# USB_Audio.net
KiCad netlist of a schematic drawn in Altium Designer
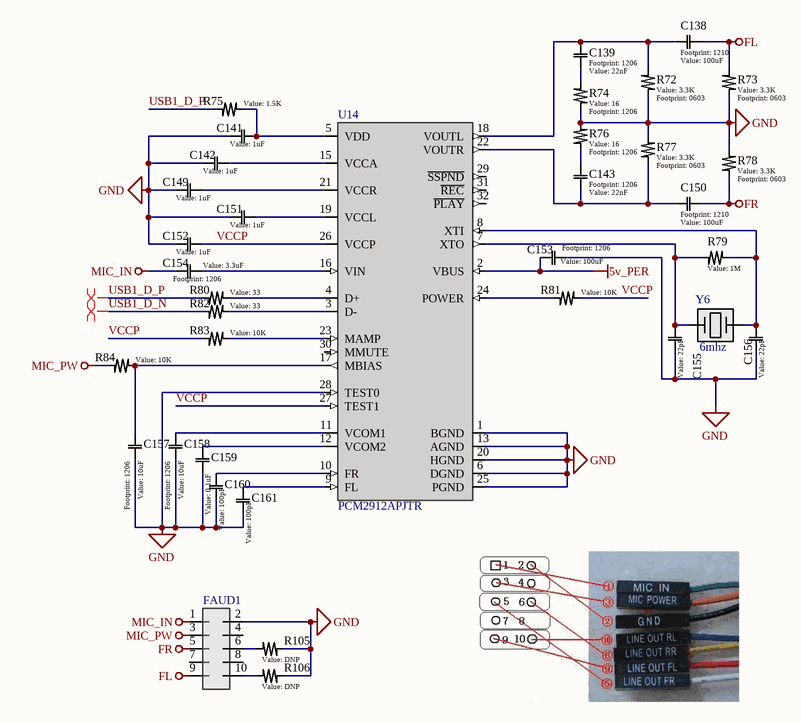
[diagram p0: USB_Audio.SchDoc]

(export (version "E")
  (design (tool "Eeschema 10.0.6"))
  (components
    (comp (ref "C138")
      (value "100uF")
      (footprint "1210")
      (fields
        (field (name "VOLTAGE") ">10V")
        (field (name "TOLERANCE") "10%")
        (field (name "Comment") "Generic Capacitor")
      )
      (libsource (lib "Capacitors") (part "Generic Capacitor"))
    )
    (comp (ref "C139")
      (value "22nF")
      (footprint "1206")
      (fields
        (field (name "VOLTAGE") ">10V")
        (field (name "TOLERANCE") "10%")
        (field (name "Comment") "Generic Capacitor")
      )
      (libsource (lib "Capacitors") (part "Generic Capacitor"))
    )
    (comp (ref "C141")
      (value "1uF")
      (footprint "0603")
      (fields
        (field (name "VOLTAGE") ">10V")
        (field (name "TOLERANCE") "10%")
        (field (name "Comment") "Generic Capacitor")
      )
      (libsource (lib "Capacitors") (part "Generic Capacitor"))
    )
    (comp (ref "C142")
      (value "1uF")
      (footprint "0603")
      (fields
        (field (name "VOLTAGE") ">10V")
        (field (name "TOLERANCE") "10%")
        (field (name "Comment") "Generic Capacitor")
      )
      (libsource (lib "Capacitors") (part "Generic Capacitor"))
    )
    (comp (ref "C143")
      (value "22nF")
      (footprint "1206")
      (fields
        (field (name "VOLTAGE") ">10V")
        (field (name "TOLERANCE") "10%")
        (field (name "Comment") "Generic Capacitor")
      )
      (libsource (lib "Capacitors") (part "Generic Capacitor"))
    )
    (comp (ref "C149")
      (value "1uF")
      (footprint "0603")
      (fields
        (field (name "VOLTAGE") ">10V")
        (field (name "TOLERANCE") "10%")
        (field (name "Comment") "Generic Capacitor")
      )
      (libsource (lib "Capacitors") (part "Generic Capacitor"))
    )
    (comp (ref "C150")
      (value "100uF")
      (footprint "1210")
      (fields
        (field (name "VOLTAGE") ">10V")
        (field (name "TOLERANCE") "10%")
        (field (name "Comment") "Generic Capacitor")
      )
      (libsource (lib "Capacitors") (part "Generic Capacitor"))
    )
    (comp (ref "C151")
      (value "1uF")
      (footprint "0603")
      (fields
        (field (name "VOLTAGE") ">10V")
        (field (name "TOLERANCE") "10%")
        (field (name "Comment") "Generic Capacitor")
      )
      (libsource (lib "Capacitors") (part "Generic Capacitor"))
    )
    (comp (ref "C152")
      (value "1uF")
      (footprint "0603")
      (fields
        (field (name "VOLTAGE") ">10V")
        (field (name "TOLERANCE") "10%")
        (field (name "Comment") "Generic Capacitor")
      )
      (libsource (lib "Capacitors") (part "Generic Capacitor"))
    )
    (comp (ref "C153")
      (value "100uF")
      (footprint "1206")
      (fields
        (field (name "VOLTAGE") ">10V")
        (field (name "TOLERANCE") "10%")
        (field (name "Comment") "Generic Capacitor")
      )
      (libsource (lib "Capacitors") (part "Generic Capacitor"))
    )
    (comp (ref "C154")
      (value "3.3uF")
      (footprint "1206")
      (fields
        (field (name "VOLTAGE") ">10V")
        (field (name "TOLERANCE") "10%")
        (field (name "Comment") "Generic Capacitor")
      )
      (libsource (lib "Capacitors") (part "Generic Capacitor"))
    )
    (comp (ref "C155")
      (value "22pF")
      (footprint "0603")
      (fields
        (field (name "VOLTAGE") ">10V")
        (field (name "TOLERANCE") "10%")
        (field (name "Comment") "Generic Capacitor")
      )
      (libsource (lib "Capacitors") (part "Generic Capacitor"))
    )
    (comp (ref "C156")
      (value "22pF")
      (footprint "0603")
      (fields
        (field (name "VOLTAGE") ">10V")
        (field (name "TOLERANCE") "10%")
        (field (name "Comment") "Generic Capacitor")
      )
      (libsource (lib "Capacitors") (part "Generic Capacitor"))
    )
    (comp (ref "C157")
      (value "10uF")
      (footprint "1206")
      (fields
        (field (name "VOLTAGE") ">10V")
        (field (name "TOLERANCE") "10%")
        (field (name "Comment") "Generic Capacitor")
      )
      (libsource (lib "Capacitors") (part "Generic Capacitor"))
    )
    (comp (ref "C158")
      (value "10uF")
      (footprint "1206")
      (fields
        (field (name "VOLTAGE") ">10V")
        (field (name "TOLERANCE") "10%")
        (field (name "Comment") "Generic Capacitor")
      )
      (libsource (lib "Capacitors") (part "Generic Capacitor"))
    )
    (comp (ref "C159")
      (value "0.1uF")
      (footprint "0603")
      (fields
        (field (name "VOLTAGE") ">10V")
        (field (name "TOLERANCE") "10%")
        (field (name "Comment") "Generic Capacitor")
      )
      (libsource (lib "Capacitors") (part "Generic Capacitor"))
    )
    (comp (ref "C160")
      (value "100pF")
      (footprint "0603")
      (fields
        (field (name "VOLTAGE") ">10V")
        (field (name "TOLERANCE") "10%")
        (field (name "Comment") "Generic Capacitor")
      )
      (libsource (lib "Capacitors") (part "Generic Capacitor"))
    )
    (comp (ref "C161")
      (value "100pF")
      (footprint "0603")
      (fields
        (field (name "VOLTAGE") ">10V")
        (field (name "TOLERANCE") "10%")
        (field (name "Comment") "Generic Capacitor")
      )
      (libsource (lib "Capacitors") (part "Generic Capacitor"))
    )
    (comp (ref "FAUD1")
      (value "10pinMobo")
      (footprint "10pinMobo")
      (description "10pin motherboard jack")
      (libsource (lib "Connectors") (part "10pinMobo"))
    )
    (comp (ref "R72")
      (value "3.3K")
      (footprint "0603")
      (fields
        (field (name "TOLERANCE") "1%")
        (field (name "POWER") "1/10W")
        (field (name "Comment") "Generic Resistor")
      )
      (libsource (lib "Resistors") (part "Generic Resistor"))
    )
    (comp (ref "R73")
      (value "3.3K")
      (footprint "0603")
      (fields
        (field (name "TOLERANCE") "1%")
        (field (name "POWER") "1/10W")
        (field (name "Comment") "Generic Resistor")
      )
      (libsource (lib "Resistors") (part "Generic Resistor"))
    )
    (comp (ref "R74")
      (value "16")
      (footprint "1206")
      (fields
        (field (name "TOLERANCE") "1%")
        (field (name "POWER") "1/10W")
        (field (name "Comment") "Generic Resistor")
      )
      (libsource (lib "Resistors") (part "Generic Resistor"))
    )
    (comp (ref "R75")
      (value "1.5K")
      (footprint "0603")
      (fields
        (field (name "TOLERANCE") "1%")
        (field (name "POWER") "1/10W")
        (field (name "Comment") "Generic Resistor")
      )
      (libsource (lib "Resistors") (part "Generic Resistor"))
    )
    (comp (ref "R76")
      (value "16")
      (footprint "1206")
      (fields
        (field (name "TOLERANCE") "1%")
        (field (name "POWER") "1/10W")
        (field (name "Comment") "Generic Resistor")
      )
      (libsource (lib "Resistors") (part "Generic Resistor"))
    )
    (comp (ref "R77")
      (value "3.3K")
      (footprint "0603")
      (fields
        (field (name "TOLERANCE") "1%")
        (field (name "POWER") "1/10W")
        (field (name "Comment") "Generic Resistor")
      )
      (libsource (lib "Resistors") (part "Generic Resistor"))
    )
    (comp (ref "R78")
      (value "3.3K")
      (footprint "0603")
      (fields
        (field (name "TOLERANCE") "1%")
        (field (name "POWER") "1/10W")
        (field (name "Comment") "Generic Resistor")
      )
      (libsource (lib "Resistors") (part "Generic Resistor"))
    )
    (comp (ref "R79")
      (value "1M")
      (footprint "0603")
      (fields
        (field (name "TOLERANCE") "1%")
        (field (name "POWER") "1/10W")
        (field (name "Comment") "Generic Resistor")
      )
      (libsource (lib "Resistors") (part "Generic Resistor"))
    )
    (comp (ref "R80")
      (value "33")
      (footprint "0603")
      (fields
        (field (name "TOLERANCE") "1%")
        (field (name "POWER") "1/10W")
        (field (name "Comment") "Generic Resistor")
      )
      (libsource (lib "Resistors") (part "Generic Resistor"))
    )
    (comp (ref "R81")
      (value "10K")
      (footprint "0603")
      (fields
        (field (name "TOLERANCE") "1%")
        (field (name "POWER") "1/10W")
        (field (name "Comment") "Generic Resistor")
      )
      (libsource (lib "Resistors") (part "Generic Resistor"))
    )
    (comp (ref "R82")
      (value "33")
      (footprint "0603")
      (fields
        (field (name "TOLERANCE") "1%")
        (field (name "POWER") "1/10W")
        (field (name "Comment") "Generic Resistor")
      )
      (libsource (lib "Resistors") (part "Generic Resistor"))
    )
    (comp (ref "R83")
      (value "10K")
      (footprint "0603")
      (fields
        (field (name "TOLERANCE") "1%")
        (field (name "POWER") "1/10W")
        (field (name "Comment") "Generic Resistor")
      )
      (libsource (lib "Resistors") (part "Generic Resistor"))
    )
    (comp (ref "R84")
      (value "10K")
      (footprint "0603")
      (fields
        (field (name "TOLERANCE") "1%")
        (field (name "POWER") "1/10W")
        (field (name "Comment") "Generic Resistor")
      )
      (libsource (lib "Resistors") (part "Generic Resistor"))
    )
    (comp (ref "R105")
      (value "DNP")
      (footprint "0603")
      (fields
        (field (name "TOLERANCE") "1%")
        (field (name "POWER") "1/10W")
        (field (name "Comment") "Generic Resistor")
      )
      (libsource (lib "Resistors") (part "Generic Resistor"))
    )
    (comp (ref "R106")
      (value "DNP")
      (footprint "0603")
      (fields
        (field (name "TOLERANCE") "1%")
        (field (name "POWER") "1/10W")
        (field (name "Comment") "Generic Resistor")
      )
      (libsource (lib "Resistors") (part "Generic Resistor"))
    )
    (comp (ref "U14")
      (value "PCM2912APJTR")
      (footprint "32-TQFP")
      (fields (field (name "MF") "Texas Instruments"))
      (libsource (lib "Misc ICs") (part "PCM2912APJTR"))
    )
    (comp (ref "Y6")
      (value "6mhz")
      (footprint "HC-49S-SMD")
      (description "6MHz Surface Mount Crystal 20pF ±20ppm ±30ppm HC-49S-SMD Crystals")
      (libsource (lib "Clock ICs") (part "H6OEL89CSC-SUGYLC-6M"))
    )
  )
  (nets
    (net (code "1") (name "/USB1_D_N") (class "Default")
      (node (ref "R82") (pin "2") (pinfunction "2_2") (pintype "passive"))
    )
    (net (code "2") (name "/USB1_D_P") (class "Default")
      (node (ref "R75") (pin "2") (pinfunction "2_2") (pintype "passive"))
      (node (ref "R80") (pin "2") (pinfunction "2_2") (pintype "passive"))
    )
    (net (code "3") (name "/VCCP") (class "Default")
      (node (ref "C152") (pin "2") (pinfunction "2_2") (pintype "passive"))
      (node (ref "R81") (pin "1") (pinfunction "1_1") (pintype "passive"))
      (node (ref "R83") (pin "2") (pinfunction "2_2") (pintype "passive"))
      (node (ref "U14") (pin "26") (pinfunction "VCCP_26") (pintype "power_in"))
      (node (ref "U14") (pin "27") (pinfunction "TEST1_27") (pintype "input"))
    )
    (net (code "4") (name "5v_PER") (class "Default")
      (node (ref "C153") (pin "1") (pinfunction "1_1") (pintype "passive"))
      (node (ref "U14") (pin "2") (pinfunction "VBUS_2") (pintype "input"))
    )
    (net (code "5") (name "FL") (class "Default")
      (node (ref "C138") (pin "1") (pinfunction "1_1") (pintype "passive"))
      (node (ref "FAUD1") (pin "9") (pinfunction "9_9") (pintype "passive"))
      (node (ref "R73") (pin "2") (pinfunction "2_2") (pintype "passive"))
    )
    (net (code "6") (name "FR") (class "Default")
      (node (ref "C150") (pin "1") (pinfunction "1_1") (pintype "passive"))
      (node (ref "FAUD1") (pin "5") (pinfunction "5_5") (pintype "passive"))
      (node (ref "R78") (pin "2") (pinfunction "2_2") (pintype "passive"))
    )
    (net (code "7") (name "GND") (class "Default")
      (node (ref "C141") (pin "1") (pinfunction "1_1") (pintype "passive"))
      (node (ref "C142") (pin "1") (pinfunction "1_1") (pintype "passive"))
      (node (ref "C149") (pin "1") (pinfunction "1_1") (pintype "passive"))
      (node (ref "C151") (pin "1") (pinfunction "1_1") (pintype "passive"))
      (node (ref "C152") (pin "1") (pinfunction "1_1") (pintype "passive"))
      (node (ref "C153") (pin "2") (pinfunction "2_2") (pintype "passive"))
      (node (ref "C155") (pin "2") (pinfunction "2_2") (pintype "passive"))
      (node (ref "C156") (pin "2") (pinfunction "2_2") (pintype "passive"))
      (node (ref "C157") (pin "2") (pinfunction "2_2") (pintype "passive"))
      (node (ref "C158") (pin "2") (pinfunction "2_2") (pintype "passive"))
      (node (ref "C159") (pin "2") (pinfunction "2_2") (pintype "passive"))
      (node (ref "C160") (pin "2") (pinfunction "2_2") (pintype "passive"))
      (node (ref "C161") (pin "2") (pinfunction "2_2") (pintype "passive"))
      (node (ref "FAUD1") (pin "2") (pinfunction "2_2") (pintype "passive"))
      (node (ref "R105") (pin "1") (pinfunction "1_1") (pintype "passive"))
      (node (ref "R106") (pin "1") (pinfunction "1_1") (pintype "passive"))
      (node (ref "R72") (pin "1") (pinfunction "1_1") (pintype "passive"))
      (node (ref "R73") (pin "1") (pinfunction "1_1") (pintype "passive"))
      (node (ref "R74") (pin "1") (pinfunction "1_1") (pintype "passive"))
      (node (ref "R76") (pin "1") (pinfunction "1_1") (pintype "passive"))
      (node (ref "R77") (pin "1") (pinfunction "1_1") (pintype "passive"))
      (node (ref "R78") (pin "1") (pinfunction "1_1") (pintype "passive"))
      (node (ref "U14") (pin "1") (pinfunction "BGND_1") (pintype "power_in"))
      (node (ref "U14") (pin "13") (pinfunction "AGND_13") (pintype "power_in"))
      (node (ref "U14") (pin "20") (pinfunction "HGND_20") (pintype "power_in"))
      (node (ref "U14") (pin "25") (pinfunction "PGND_25") (pintype "power_in"))
      (node (ref "U14") (pin "28") (pinfunction "TEST0_28") (pintype "input"))
      (node (ref "U14") (pin "6") (pinfunction "DGND_6") (pintype "power_in"))
    )
    (net (code "8") (name "MIC_IN") (class "Default")
      (node (ref "C154") (pin "2") (pinfunction "2_2") (pintype "passive"))
      (node (ref "FAUD1") (pin "1") (pinfunction "1_1") (pintype "passive"))
    )
    (net (code "9") (name "MIC_PW") (class "Default")
      (node (ref "FAUD1") (pin "3") (pinfunction "3_3") (pintype "passive"))
      (node (ref "R84") (pin "2") (pinfunction "2_2") (pintype "passive"))
    )
    (net (code "10") (name "Net-(C139-Pad2)") (class "Default")
      (node (ref "C139") (pin "2") (pinfunction "2_2") (pintype "passive"))
      (node (ref "R74") (pin "2") (pinfunction "2_2") (pintype "passive"))
    )
    (net (code "11") (name "Net-(C143-Pad2)") (class "Default")
      (node (ref "C143") (pin "2") (pinfunction "2_2") (pintype "passive"))
      (node (ref "R76") (pin "2") (pinfunction "2_2") (pintype "passive"))
    )
    (net (code "12") (name "Net-(FAUD1-Pad6)") (class "Default")
      (node (ref "FAUD1") (pin "6") (pinfunction "6_6") (pintype "passive"))
      (node (ref "R105") (pin "2") (pinfunction "2_2") (pintype "passive"))
    )
    (net (code "13") (name "Net-(FAUD1-Pad10)") (class "Default")
      (node (ref "FAUD1") (pin "10") (pinfunction "10_10") (pintype "passive"))
      (node (ref "R106") (pin "2") (pinfunction "2_2") (pintype "passive"))
    )
    (net (code "14") (name "Net-(U14-D+)") (class "Default")
      (node (ref "R80") (pin "1") (pinfunction "1_1") (pintype "passive"))
      (node (ref "U14") (pin "4") (pinfunction "D+_4") (pintype "bidirectional"))
    )
    (net (code "15") (name "Net-(U14-D-)") (class "Default")
      (node (ref "R82") (pin "1") (pinfunction "1_1") (pintype "passive"))
      (node (ref "U14") (pin "3") (pinfunction "D-_3") (pintype "bidirectional"))
    )
    (net (code "16") (name "Net-(U14-FL)") (class "Default")
      (node (ref "C161") (pin "1") (pinfunction "1_1") (pintype "passive"))
      (node (ref "U14") (pin "9") (pinfunction "FL_9") (pintype "input"))
    )
    (net (code "17") (name "Net-(U14-FR)") (class "Default")
      (node (ref "C160") (pin "1") (pinfunction "1_1") (pintype "passive"))
      (node (ref "U14") (pin "10") (pinfunction "FR_10") (pintype "input"))
    )
    (net (code "18") (name "Net-(U14-MAMP)") (class "Default")
      (node (ref "R83") (pin "1") (pinfunction "1_1") (pintype "passive"))
      (node (ref "U14") (pin "23") (pinfunction "MAMP_23") (pintype "input"))
    )
    (net (code "19") (name "Net-(U14-MBIAS)") (class "Default")
      (node (ref "C157") (pin "1") (pinfunction "1_1") (pintype "passive"))
      (node (ref "R84") (pin "1") (pinfunction "1_1") (pintype "passive"))
      (node (ref "U14") (pin "17") (pinfunction "MBIAS_17") (pintype "output"))
    )
    (net (code "20") (name "Net-(U14-POWER)") (class "Default")
      (node (ref "R81") (pin "2") (pinfunction "2_2") (pintype "passive"))
      (node (ref "U14") (pin "24") (pinfunction "POWER_24") (pintype "input"))
    )
    (net (code "21") (name "Net-(U14-VCCA)") (class "Default")
      (node (ref "C142") (pin "2") (pinfunction "2_2") (pintype "passive"))
      (node (ref "U14") (pin "15") (pinfunction "VCCA_15") (pintype "power_in"))
    )
    (net (code "22") (name "Net-(U14-VCCL)") (class "Default")
      (node (ref "C151") (pin "2") (pinfunction "2_2") (pintype "passive"))
      (node (ref "U14") (pin "19") (pinfunction "VCCL_19") (pintype "power_in"))
    )
    (net (code "23") (name "Net-(U14-VCCR)") (class "Default")
      (node (ref "C149") (pin "2") (pinfunction "2_2") (pintype "passive"))
      (node (ref "U14") (pin "21") (pinfunction "VCCR_21") (pintype "power_in"))
    )
    (net (code "24") (name "Net-(U14-VCOM1)") (class "Default")
      (node (ref "C158") (pin "1") (pinfunction "1_1") (pintype "passive"))
      (node (ref "U14") (pin "11") (pinfunction "VCOM1_11") (pintype "power_in"))
    )
    (net (code "25") (name "Net-(U14-VCOM2)") (class "Default")
      (node (ref "C159") (pin "1") (pinfunction "1_1") (pintype "passive"))
      (node (ref "U14") (pin "12") (pinfunction "VCOM2_12") (pintype "power_in"))
    )
    (net (code "26") (name "Net-(U14-VDD)") (class "Default")
      (node (ref "C141") (pin "2") (pinfunction "2_2") (pintype "passive"))
      (node (ref "R75") (pin "1") (pinfunction "1_1") (pintype "passive"))
      (node (ref "U14") (pin "5") (pinfunction "VDD_5") (pintype "power_in"))
    )
    (net (code "27") (name "Net-(U14-VIN)") (class "Default")
      (node (ref "C154") (pin "1") (pinfunction "1_1") (pintype "passive"))
      (node (ref "U14") (pin "16") (pinfunction "VIN_16") (pintype "input"))
    )
    (net (code "28") (name "Net-(U14-VOUTL)") (class "Default")
      (node (ref "C138") (pin "2") (pinfunction "2_2") (pintype "passive"))
      (node (ref "C139") (pin "1") (pinfunction "1_1") (pintype "passive"))
      (node (ref "R72") (pin "2") (pinfunction "2_2") (pintype "passive"))
      (node (ref "U14") (pin "18") (pinfunction "VOUTL_18") (pintype "output"))
    )
    (net (code "29") (name "Net-(U14-VOUTR)") (class "Default")
      (node (ref "C143") (pin "1") (pinfunction "1_1") (pintype "passive"))
      (node (ref "C150") (pin "2") (pinfunction "2_2") (pintype "passive"))
      (node (ref "R77") (pin "2") (pinfunction "2_2") (pintype "passive"))
      (node (ref "U14") (pin "22") (pinfunction "VOUTR_22") (pintype "output"))
    )
    (net (code "30") (name "Net-(U14-XTI)") (class "Default")
      (node (ref "C156") (pin "1") (pinfunction "1_1") (pintype "passive"))
      (node (ref "R79") (pin "2") (pinfunction "2_2") (pintype "passive"))
      (node (ref "U14") (pin "8") (pinfunction "XTI_8") (pintype "input"))
      (node (ref "Y6") (pin "2") (pintype "passive"))
    )
    (net (code "31") (name "Net-(U14-XTO)") (class "Default")
      (node (ref "C155") (pin "1") (pinfunction "1_1") (pintype "passive"))
      (node (ref "R79") (pin "1") (pinfunction "1_1") (pintype "passive"))
      (node (ref "U14") (pin "7") (pinfunction "XTO_7") (pintype "output"))
      (node (ref "Y6") (pin "1") (pintype "passive"))
    )
    (net (code "32") (name "unconnected-(FAUD1-Pad4)") (class "Default")
      (node (ref "FAUD1") (pin "4") (pinfunction "4_4") (pintype "passive"))
    )
    (net (code "33") (name "unconnected-(FAUD1-Pad7)") (class "Default")
      (node (ref "FAUD1") (pin "7") (pinfunction "7_7") (pintype "passive"))
    )
    (net (code "34") (name "unconnected-(FAUD1-Pad8)") (class "Default")
      (node (ref "FAUD1") (pin "8") (pinfunction "8_8") (pintype "passive"))
    )
    (net (code "35") (name "unconnected-(U14-MMUTE-Pad30)") (class "Default")
      (node (ref "U14") (pin "30") (pinfunction "MMUTE_30") (pintype "input"))
    )
    (net (code "36") (name "unconnected-(U14-~{PLAY}-Pad32)") (class "Default")
      (node (ref "U14") (pin "32") (pinfunction "~{PLAY}_32") (pintype "output"))
    )
    (net (code "37") (name "unconnected-(U14-~{REC}-Pad31)") (class "Default")
      (node (ref "U14") (pin "31") (pinfunction "~{REC}_31") (pintype "output"))
    )
    (net (code "38") (name "unconnected-(U14-~{SSPND}-Pad29)") (class "Default")
      (node (ref "U14") (pin "29") (pinfunction "~{SSPND}_29") (pintype "output"))
    )
  )
)
